# pumpController.net
KiCad netlist of a schematic drawn in Altium Designer
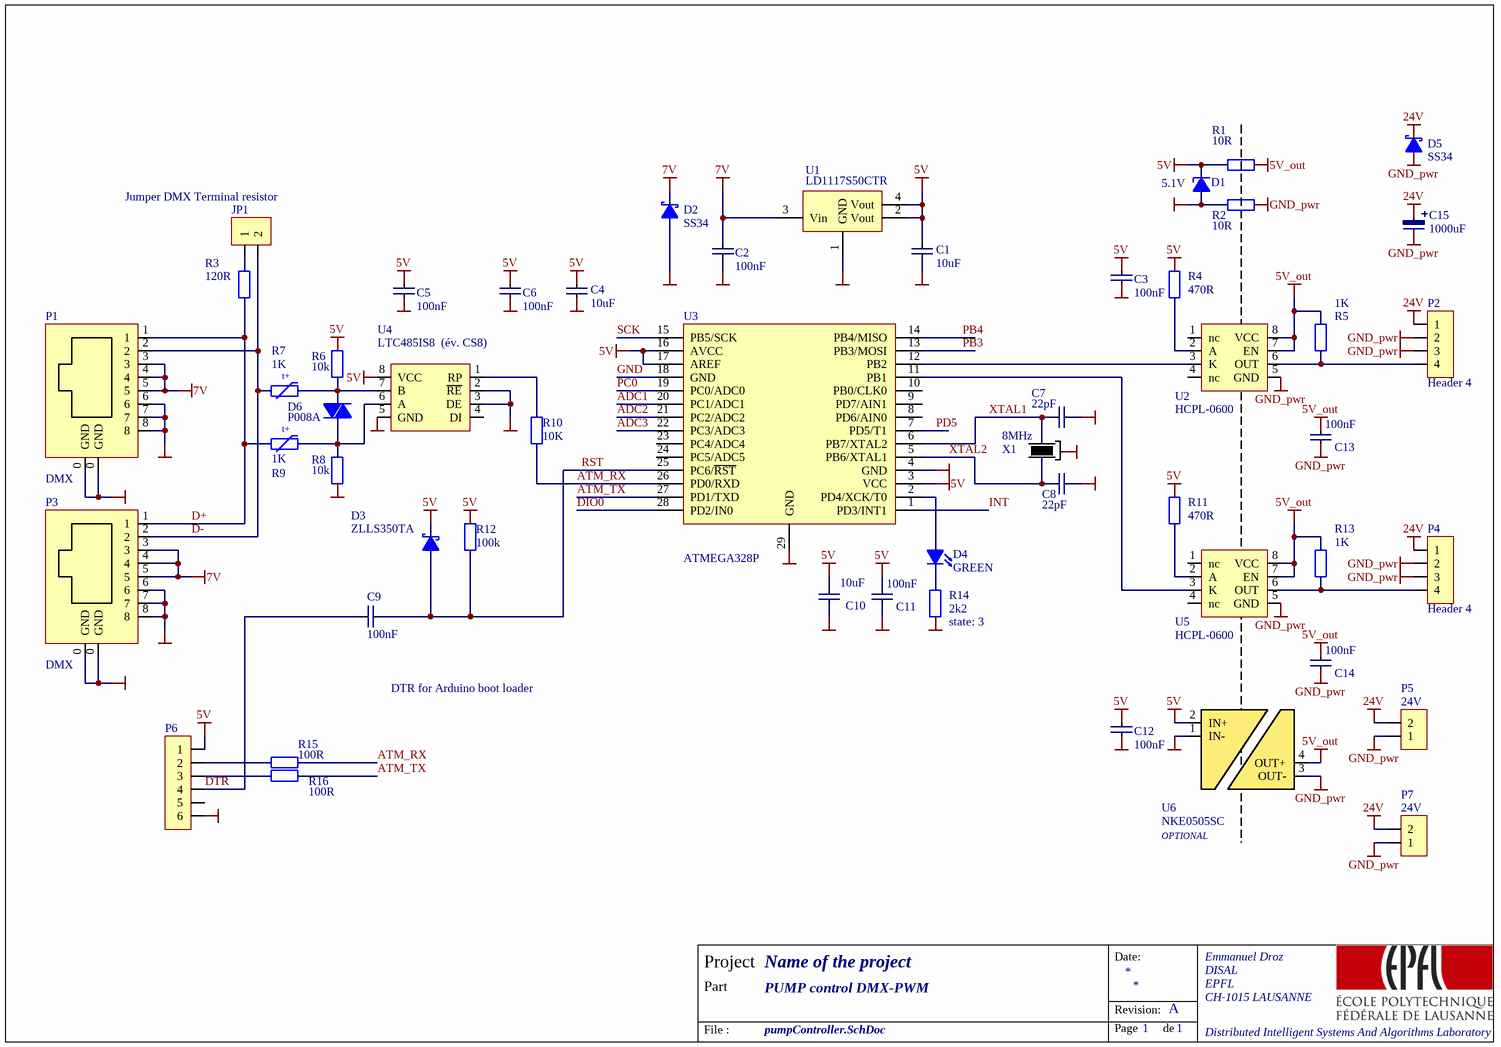
[diagram p0: pumpController.SchDoc]

(export (version "E")
  (design (tool "Eeschema 10.0.6"))
  (components
    (comp (ref "C1")
      (value "10uF")
      (footprint "SwissArmyKnife:0805")
      (description "Capacitor")
      (libsource (lib "SwissArmyKnife") (part "C"))
    )
    (comp (ref "C2")
      (value "100nF")
      (footprint "SwissArmyKnife:0603")
      (description "Capacitor")
      (libsource (lib "SwissArmyKnife") (part "C"))
    )
    (comp (ref "C3")
      (value "100nF")
      (footprint "SwissArmyKnife:0603")
      (description "Capacitor")
      (libsource (lib "SwissArmyKnife") (part "C"))
    )
    (comp (ref "C4")
      (value "10uF")
      (footprint "SwissArmyKnife:0805")
      (description "Capacitor")
      (libsource (lib "SwissArmyKnife") (part "C"))
    )
    (comp (ref "C5")
      (value "100nF")
      (footprint "SwissArmyKnife:0603")
      (description "Capacitor")
      (libsource (lib "SwissArmyKnife") (part "C"))
    )
    (comp (ref "C6")
      (value "100nF")
      (footprint "SwissArmyKnife:0603")
      (description "Capacitor")
      (libsource (lib "SwissArmyKnife") (part "C"))
    )
    (comp (ref "C7")
      (value "22pF")
      (footprint "SwissArmyKnife:0603")
      (description "Capacitor")
      (libsource (lib "SwissArmyKnife") (part "C"))
    )
    (comp (ref "C8")
      (value "22pF")
      (footprint "SwissArmyKnife:0603")
      (description "Capacitor")
      (libsource (lib "SwissArmyKnife") (part "C"))
    )
    (comp (ref "C9")
      (value "100nF")
      (footprint "SwissArmyKnife:0603")
      (description "Capacitor")
      (libsource (lib "SwissArmyKnife") (part "C"))
    )
    (comp (ref "C10")
      (value "10uF")
      (footprint "SwissArmyKnife:0805")
      (description "Capacitor")
      (libsource (lib "SwissArmyKnife") (part "C"))
    )
    (comp (ref "C11")
      (value "100nF")
      (footprint "SwissArmyKnife:0603")
      (description "Capacitor")
      (libsource (lib "SwissArmyKnife") (part "C"))
    )
    (comp (ref "C12")
      (value "100nF")
      (footprint "SwissArmyKnife:0603")
      (description "Capacitor")
      (libsource (lib "SwissArmyKnife") (part "C"))
    )
    (comp (ref "C13")
      (value "100nF")
      (footprint "SwissArmyKnife:0603")
      (description "Capacitor")
      (libsource (lib "SwissArmyKnife") (part "C"))
    )
    (comp (ref "C14")
      (value "100nF")
      (footprint "SwissArmyKnife:0603")
      (description "Capacitor")
      (libsource (lib "SwissArmyKnife") (part "C"))
    )
    (comp (ref "C15")
      (value "1000uF")
      (footprint "CapaRadialD12.5H20F5")
      (description "Capacitor")
      (libsource (lib "SwissArmyKnife") (part "Cp"))
    )
    (comp (ref "D1")
      (value "5.1V")
      (footprint "MELF")
      (description "Diode")
      (fields (field (name "Comment") "not mounted"))
      (libsource (lib "electroz") (part "D_Zener"))
    )
    (comp (ref "D2")
      (value "SS34")
      (footprint "swissarmyknife:MELF")
      (description "Schottky Diode 1A 0.5V 20V")
      (fields (field (name "NAME") "SS34"))
      (libsource (lib "disaldb") (part "D_schottky"))
    )
    (comp (ref "D3")
      (value "ZLLS350TA")
      (footprint "0603pol")
      (description "Shottky diode")
      (libsource (lib "SwissArmyKnife") (part "D_schottky"))
    )
    (comp (ref "D4")
      (value "GREEN")
      (footprint "SwissArmyKnife:0805pol")
      (description "LED green")
      (libsource (lib "SwissArmyKnife") (part "LED"))
    )
    (comp (ref "D5")
      (value "SS34")
      (footprint "swissarmyknife:MELF")
      (description "Schottky Diode 1A 0.5V 20V")
      (fields (field (name "NAME") "SS34"))
      (libsource (lib "disaldb") (part "D_schottky"))
    )
    (comp (ref "D6")
      (value "P008A")
      (footprint "DO-214")
      (description "Diac")
      (libsource (lib "SwissArmyKnife") (part "D_Diac"))
    )
    (comp (ref "JP1")
      (value "Jumper DMX Terminal resistor")
      (footprint "electroz:Jumper")
      (description "Header, 4-Pin, Dual row")
      (libsource (lib "electroz") (part "Header 2"))
    )
    (comp (ref "P1")
      (value "DMX")
      (footprint "SwissArmyKnife:RJ45__socket_right")
      (libsource (lib "SwissArmyKnife") (part "RJ45"))
    )
    (comp (ref "P2")
      (value "Header 4")
      (footprint "electroz:PHO_3.81_180_4x")
      (description "Header, 4-Pin, single row")
      (fields (field (name "PUBLISHER") "Altium Limited"))
      (libsource (lib "electroz") (part "Header 4"))
    )
    (comp (ref "P3")
      (value "DMX")
      (footprint "SwissArmyKnife:RJ45__socket_right")
      (libsource (lib "SwissArmyKnife") (part "RJ45"))
    )
    (comp (ref "P4")
      (value "Header 4")
      (footprint "electroz:PHO_3.81_180_4x")
      (description "Header, 4-Pin, single row")
      (fields (field (name "PUBLISHER") "Altium Limited"))
      (libsource (lib "electroz") (part "Header 4"))
    )
    (comp (ref "P5")
      (value "24V")
      (footprint "electroz:ALIME 5_08 180")
      (description "Header, 4-Pin, Dual row")
      (fields (field (name "PUBLISHER") "Altium Limited"))
      (libsource (lib "electroz") (part "Header 2"))
    )
    (comp (ref "P6")
      (value "Header 6")
      (footprint "Header6_1.25_micro_JST_Axial")
      (description "Header,6-Pin")
      (fields (field (name "PUBLISHER") "Altium Limited"))
      (libsource (lib "SwissArmyKnife") (part "Header 6"))
    )
    (comp (ref "P7")
      (value "24V")
      (footprint "electroz:ALIME 5_08 180")
      (description "Header, 4-Pin, Dual row")
      (fields (field (name "PUBLISHER") "Altium Limited"))
      (libsource (lib "electroz") (part "Header 2"))
    )
    (comp (ref "R1")
      (value "10R")
      (footprint "swissarmyknife:0603")
      (description "Resistor")
      (libsource (lib "") (part "R_2"))
    )
    (comp (ref "R2")
      (value "10R")
      (footprint "swissarmyknife:0603")
      (description "Resistor")
      (libsource (lib "") (part "R_2"))
    )
    (comp (ref "R3")
      (value "120R")
      (footprint "swissarmyknife:1206")
      (description "Resistor")
      (libsource (lib "") (part "R_1"))
    )
    (comp (ref "R4")
      (value "470R")
      (footprint "swissarmyknife:0603")
      (description "Resistor")
      (libsource (lib "") (part "R_1"))
    )
    (comp (ref "R5")
      (value "1K")
      (footprint "swissarmyknife:0603")
      (description "Resistor")
      (libsource (lib "") (part "R_1"))
    )
    (comp (ref "R6")
      (value "10k")
      (footprint "swissarmyknife:0603")
      (description "Resistor")
      (libsource (lib "") (part "R_1"))
    )
    (comp (ref "R7")
      (value "1K")
      (footprint "swissarmyknife:MZ6")
      (description "Resistor PTC")
      (libsource (lib "SwissArmyKnife") (part "R_ptc"))
    )
    (comp (ref "R8")
      (value "10k")
      (footprint "swissarmyknife:0603")
      (description "Resistor")
      (libsource (lib "") (part "R_1"))
    )
    (comp (ref "R9")
      (value "1K")
      (footprint "swissarmyknife:MZ6")
      (description "Resistor PTC")
      (libsource (lib "SwissArmyKnife") (part "R_ptc"))
    )
    (comp (ref "R10")
      (value "10K")
      (footprint "swissarmyknife:0603")
      (description "Resistor")
      (libsource (lib "") (part "R_1"))
    )
    (comp (ref "R11")
      (value "470R")
      (footprint "swissarmyknife:0603")
      (description "Resistor")
      (libsource (lib "") (part "R_1"))
    )
    (comp (ref "R12")
      (value "100k")
      (footprint "swissarmyknife:0603")
      (description "Resistor")
      (libsource (lib "") (part "R_2"))
    )
    (comp (ref "R13")
      (value "1K")
      (footprint "swissarmyknife:0603")
      (description "Resistor")
      (libsource (lib "") (part "R_1"))
    )
    (comp (ref "R14")
      (value "2k2")
      (footprint "swissarmyknife:0603")
      (description "Resistor")
      (fields (field (name "STATE") "3"))
      (libsource (lib "") (part "R_1"))
    )
    (comp (ref "R15")
      (value "100R")
      (footprint "swissarmyknife:0603")
      (description "Resistor")
      (libsource (lib "SwissArmyKnife") (part "R"))
    )
    (comp (ref "R16")
      (value "100R")
      (footprint "swissarmyknife:0603")
      (description "Resistor")
      (libsource (lib "SwissArmyKnife") (part "R"))
    )
    (comp (ref "U1")
      (value "LD1117S50CTR")
      (footprint "SOT-223")
      (description "Linear regulator")
      (fields (field (name "NAME") "LD1117S50CTR"))
      (libsource (lib "SwissArmyKnife") (part "STAB_x17"))
    )
    (comp (ref "U2")
      (value "HCPL-0600")
      (footprint "electroz:so-8")
      (description "Logical optocoupler single SO8")
      (libsource (lib "electroz") (part "HCPL-0600"))
    )
    (comp (ref "U3")
      (value "ATMEGA328P")
      (footprint "ATM328P_MMH")
      (libsource (lib "LoRa_I2C_Lib") (part "ATM328P"))
    )
    (comp (ref "U4")
      (value "LTC485IS8  (év. CS8)")
      (footprint "SwissArmyKnife:so-8")
      (libsource (lib "electroz") (part "LTC485CS8"))
    )
    (comp (ref "U5")
      (value "HCPL-0600")
      (footprint "electroz:so-8")
      (description "Logical optocoupler single SO8")
      (libsource (lib "electroz") (part "HCPL-0600"))
    )
    (comp (ref "U6")
      (value "NKE0505SC")
      (footprint "SIL4")
      (description "Isolated power supply")
      (libsource (lib "electroz") (part "DCDCisolated"))
    )
    (comp (ref "X1") (value "8MHz") (footprint "osc") (libsource (lib "SwissArmyKnife") (part "Quartz")))
  )
  (nets
    (net (code "1") (name "/ADC1") (class "Default")
      (node (ref "U3") (pin "20") (pinfunction "PC1/ADC1_20") (pintype "passive"))
    )
    (net (code "2") (name "/ADC2") (class "Default")
      (node (ref "U3") (pin "21") (pinfunction "PC2/ADC2_21") (pintype "passive"))
    )
    (net (code "3") (name "/ADC3") (class "Default")
      (node (ref "U3") (pin "22") (pinfunction "PC3/ADC3_22") (pintype "passive"))
    )
    (net (code "4") (name "/ATM_RX") (class "Default")
      (node (ref "R10") (pin "2") (pinfunction "2_2") (pintype "passive"))
      (node (ref "R15") (pin "2") (pinfunction "2_2") (pintype "passive"))
      (node (ref "U3") (pin "26") (pinfunction "PD0/RXD_26") (pintype "passive"))
    )
    (net (code "5") (name "/ATM_TX") (class "Default")
      (node (ref "R16") (pin "2") (pinfunction "2_2") (pintype "passive"))
      (node (ref "U3") (pin "27") (pinfunction "PD1/TXD_27") (pintype "passive"))
    )
    (net (code "6") (name "/D+") (class "Default")
      (node (ref "P1") (pin "1") (pinfunction "1_1") (pintype "passive"))
      (node (ref "P3") (pin "1") (pinfunction "1_1") (pintype "passive"))
      (node (ref "R3") (pin "2") (pinfunction "2_2") (pintype "passive"))
      (node (ref "R9") (pin "1") (pinfunction "1_1") (pintype "passive"))
    )
    (net (code "7") (name "/D-") (class "Default")
      (node (ref "JP1") (pin "2") (pinfunction "2_2") (pintype "passive"))
      (node (ref "P1") (pin "2") (pinfunction "2_2") (pintype "passive"))
      (node (ref "P3") (pin "2") (pinfunction "2_2") (pintype "passive"))
      (node (ref "R7") (pin "1") (pinfunction "1_1") (pintype "passive"))
    )
    (net (code "8") (name "/DIO0") (class "Default")
      (node (ref "U3") (pin "28") (pinfunction "PD2/IN0_28") (pintype "passive"))
    )
    (net (code "9") (name "/DTR") (class "Default")
      (node (ref "C9") (pin "2") (pinfunction "2_2") (pintype "passive"))
      (node (ref "P6") (pin "4") (pinfunction "4_4") (pintype "passive"))
    )
    (net (code "10") (name "/INT") (class "Default")
      (node (ref "U3") (pin "1") (pinfunction "PD3/INT1_1") (pintype "passive"))
    )
    (net (code "11") (name "/PB3") (class "Default")
      (node (ref "U3") (pin "13") (pinfunction "PB3/MOSI_13") (pintype "passive"))
    )
    (net (code "12") (name "/PB4") (class "Default")
      (node (ref "U3") (pin "14") (pinfunction "PB4/MISO_14") (pintype "passive"))
    )
    (net (code "13") (name "/PC0") (class "Default")
      (node (ref "U3") (pin "19") (pinfunction "PC0/ADC0_19") (pintype "passive"))
    )
    (net (code "14") (name "/PD5") (class "Default")
      (node (ref "U3") (pin "7") (pinfunction "PD5/T1_7") (pintype "passive"))
    )
    (net (code "15") (name "/RST") (class "Default")
      (node (ref "C9") (pin "1") (pinfunction "1_1") (pintype "passive"))
      (node (ref "D3") (pin "1") (pinfunction "A_1") (pintype "passive"))
      (node (ref "R12") (pin "1") (pinfunction "1_1") (pintype "passive"))
      (node (ref "U3") (pin "25") (pinfunction "PC6/~{RST}_25") (pintype "passive"))
    )
    (net (code "16") (name "/SCK") (class "Default")
      (node (ref "U3") (pin "15") (pinfunction "PB5/SCK_15") (pintype "passive"))
    )
    (net (code "17") (name "/XTAL1") (class "Default")
      (node (ref "C7") (pin "1") (pinfunction "1_1") (pintype "passive"))
      (node (ref "U3") (pin "6") (pinfunction "PB7/XTAL2_6") (pintype "passive"))
      (node (ref "X1") (pin "1") (pinfunction "1_1") (pintype "passive"))
    )
    (net (code "18") (name "/XTAL2") (class "Default")
      (node (ref "C8") (pin "1") (pinfunction "1_1") (pintype "passive"))
      (node (ref "U3") (pin "5") (pinfunction "PB6/XTAL1_5") (pintype "passive"))
      (node (ref "X1") (pin "2") (pinfunction "2_2") (pintype "passive"))
    )
    (net (code "19") (name "5V") (class "Default")
      (node (ref "C1") (pin "1") (pinfunction "1_1") (pintype "passive"))
      (node (ref "C10") (pin "1") (pinfunction "1_1") (pintype "passive"))
      (node (ref "C11") (pin "1") (pinfunction "1_1") (pintype "passive"))
      (node (ref "C12") (pin "2") (pinfunction "2_2") (pintype "passive"))
      (node (ref "C3") (pin "2") (pinfunction "2_2") (pintype "passive"))
      (node (ref "C4") (pin "1") (pinfunction "1_1") (pintype "passive"))
      (node (ref "C5") (pin "2") (pinfunction "2_2") (pintype "passive"))
      (node (ref "C6") (pin "2") (pinfunction "2_2") (pintype "passive"))
      (node (ref "D1") (pin "2") (pinfunction "K_2") (pintype "passive"))
      (node (ref "D3") (pin "2") (pinfunction "K_2") (pintype "passive"))
      (node (ref "P6") (pin "1") (pinfunction "1_1") (pintype "passive"))
      (node (ref "R1") (pin "1") (pinfunction "1_1") (pintype "passive"))
      (node (ref "R11") (pin "1") (pinfunction "1_1") (pintype "passive"))
      (node (ref "R12") (pin "2") (pinfunction "2_2") (pintype "passive"))
      (node (ref "R4") (pin "1") (pinfunction "1_1") (pintype "passive"))
      (node (ref "R6") (pin "1") (pinfunction "1_1") (pintype "passive"))
      (node (ref "U1") (pin "2") (pinfunction "Vout_2") (pintype "power_in"))
      (node (ref "U1") (pin "4") (pinfunction "Vout_4") (pintype "passive"))
      (node (ref "U3") (pin "16") (pinfunction "AVCC_16") (pintype "passive"))
      (node (ref "U3") (pin "17") (pinfunction "AREF_17") (pintype "passive"))
      (node (ref "U3") (pin "3") (pinfunction "VCC_3") (pintype "passive"))
      (node (ref "U4") (pin "8") (pinfunction "VCC_8") (pintype "passive"))
      (node (ref "U6") (pin "2") (pinfunction "IN+_2") (pintype "passive"))
    )
    (net (code "20") (name "5V_out") (class "Default")
      (node (ref "C13") (pin "1") (pinfunction "1_1") (pintype "passive"))
      (node (ref "C14") (pin "1") (pinfunction "1_1") (pintype "passive"))
      (node (ref "R1") (pin "2") (pinfunction "2_2") (pintype "passive"))
      (node (ref "R13") (pin "1") (pinfunction "1_1") (pintype "passive"))
      (node (ref "R5") (pin "1") (pinfunction "1_1") (pintype "passive"))
      (node (ref "U2") (pin "7") (pinfunction "EN_7") (pintype "passive"))
      (node (ref "U2") (pin "8") (pinfunction "VCC_8") (pintype "passive"))
      (node (ref "U5") (pin "7") (pinfunction "EN_7") (pintype "passive"))
      (node (ref "U5") (pin "8") (pinfunction "VCC_8") (pintype "passive"))
      (node (ref "U6") (pin "4") (pinfunction "OUT+_4") (pintype "passive"))
    )
    (net (code "21") (name "7V") (class "Default")
      (node (ref "C2") (pin "2") (pinfunction "2_2") (pintype "passive"))
      (node (ref "D2") (pin "2") (pinfunction "K_2") (pintype "passive"))
      (node (ref "P1") (pin "3") (pinfunction "3_3") (pintype "passive"))
      (node (ref "P1") (pin "4") (pinfunction "4_4") (pintype "passive"))
      (node (ref "P1") (pin "5") (pinfunction "5_5") (pintype "passive"))
      (node (ref "P3") (pin "3") (pinfunction "3_3") (pintype "passive"))
      (node (ref "P3") (pin "4") (pinfunction "4_4") (pintype "passive"))
      (node (ref "P3") (pin "5") (pinfunction "5_5") (pintype "passive"))
      (node (ref "U1") (pin "3") (pinfunction "Vin_3") (pintype "power_in"))
    )
    (net (code "22") (name "24V") (class "Default")
      (node (ref "C15") (pin "2") (pinfunction "2_2") (pintype "passive"))
      (node (ref "D5") (pin "2") (pinfunction "K_2") (pintype "passive"))
      (node (ref "P2") (pin "1") (pinfunction "1_1") (pintype "passive"))
      (node (ref "P4") (pin "1") (pinfunction "1_1") (pintype "passive"))
      (node (ref "P5") (pin "2") (pinfunction "2_2") (pintype "passive"))
      (node (ref "P7") (pin "2") (pinfunction "2_2") (pintype "passive"))
    )
    (net (code "23") (name "GND") (class "Default")
      (node (ref "C1") (pin "2") (pinfunction "2_2") (pintype "passive"))
      (node (ref "C10") (pin "2") (pinfunction "2_2") (pintype "passive"))
      (node (ref "C11") (pin "2") (pinfunction "2_2") (pintype "passive"))
      (node (ref "C12") (pin "1") (pinfunction "1_1") (pintype "passive"))
      (node (ref "C2") (pin "1") (pinfunction "1_1") (pintype "passive"))
      (node (ref "C3") (pin "1") (pinfunction "1_1") (pintype "passive"))
      (node (ref "C4") (pin "2") (pinfunction "2_2") (pintype "passive"))
      (node (ref "C5") (pin "1") (pinfunction "1_1") (pintype "passive"))
      (node (ref "C6") (pin "1") (pinfunction "1_1") (pintype "passive"))
      (node (ref "C7") (pin "2") (pinfunction "2_2") (pintype "passive"))
      (node (ref "C8") (pin "2") (pinfunction "2_2") (pintype "passive"))
      (node (ref "D1") (pin "1") (pinfunction "A_1") (pintype "passive"))
      (node (ref "D2") (pin "1") (pinfunction "A_1") (pintype "passive"))
      (node (ref "P1") (pin "0") (pinfunction "GND_0") (pintype "passive"))
      (node (ref "P1") (pin "6") (pinfunction "6_6") (pintype "passive"))
      (node (ref "P1") (pin "7") (pinfunction "7_7") (pintype "passive"))
      (node (ref "P1") (pin "8") (pinfunction "8_8") (pintype "passive"))
      (node (ref "P3") (pin "0") (pinfunction "GND_0") (pintype "passive"))
      (node (ref "P3") (pin "6") (pinfunction "6_6") (pintype "passive"))
      (node (ref "P3") (pin "7") (pinfunction "7_7") (pintype "passive"))
      (node (ref "P3") (pin "8") (pinfunction "8_8") (pintype "passive"))
      (node (ref "P6") (pin "6") (pinfunction "6_6") (pintype "passive"))
      (node (ref "R14") (pin "2") (pinfunction "2_2") (pintype "passive"))
      (node (ref "R2") (pin "1") (pinfunction "1_1") (pintype "passive"))
      (node (ref "R8") (pin "2") (pinfunction "2_2") (pintype "passive"))
      (node (ref "U1") (pin "1") (pinfunction "GND_1") (pintype "passive"))
      (node (ref "U3") (pin "18") (pinfunction "GND_18") (pintype "passive"))
      (node (ref "U3") (pin "29") (pinfunction "GND_29") (pintype "passive"))
      (node (ref "U3") (pin "4") (pinfunction "GND_4") (pintype "passive"))
      (node (ref "U4") (pin "2") (pinfunction "~{RE}_2") (pintype "passive"))
      (node (ref "U4") (pin "3") (pinfunction "DE_3") (pintype "passive"))
      (node (ref "U4") (pin "5") (pinfunction "GND_5") (pintype "passive"))
      (node (ref "U6") (pin "1") (pinfunction "IN-_1") (pintype "passive"))
      (node (ref "X1") (pin "3") (pinfunction "3_3") (pintype "passive"))
    )
    (net (code "24") (name "GND_pwr") (class "Default")
      (node (ref "C13") (pin "2") (pinfunction "2_2") (pintype "passive"))
      (node (ref "C14") (pin "2") (pinfunction "2_2") (pintype "passive"))
      (node (ref "C15") (pin "1") (pinfunction "1_1") (pintype "passive"))
      (node (ref "D5") (pin "1") (pinfunction "A_1") (pintype "passive"))
      (node (ref "P2") (pin "2") (pinfunction "2_2") (pintype "passive"))
      (node (ref "P2") (pin "3") (pinfunction "3_3") (pintype "passive"))
      (node (ref "P4") (pin "2") (pinfunction "2_2") (pintype "passive"))
      (node (ref "P4") (pin "3") (pinfunction "3_3") (pintype "passive"))
      (node (ref "P5") (pin "1") (pinfunction "1_1") (pintype "passive"))
      (node (ref "P7") (pin "1") (pinfunction "1_1") (pintype "passive"))
      (node (ref "R2") (pin "2") (pinfunction "2_2") (pintype "passive"))
      (node (ref "U2") (pin "5") (pinfunction "GND_5") (pintype "passive"))
      (node (ref "U5") (pin "5") (pinfunction "GND_5") (pintype "passive"))
      (node (ref "U6") (pin "3") (pinfunction "OUT-_3") (pintype "passive"))
    )
    (net (code "25") (name "Net-(D4-A)") (class "Default")
      (node (ref "D4") (pin "1") (pinfunction "A_1") (pintype "passive"))
      (node (ref "U3") (pin "2") (pinfunction "PD4/XCK/T0_2") (pintype "passive"))
    )
    (net (code "26") (name "Net-(D4-K)") (class "Default")
      (node (ref "D4") (pin "2") (pinfunction "K_2") (pintype "passive"))
      (node (ref "R14") (pin "1") (pinfunction "1_1") (pintype "passive"))
    )
    (net (code "27") (name "Net-(D6-A)") (class "Default")
      (node (ref "D6") (pin "1") (pinfunction "A_1") (pintype "passive"))
      (node (ref "R6") (pin "2") (pinfunction "2_2") (pintype "passive"))
      (node (ref "R7") (pin "2") (pinfunction "2_2") (pintype "passive"))
      (node (ref "U4") (pin "7") (pinfunction "B_7") (pintype "passive"))
    )
    (net (code "28") (name "Net-(D6-K)") (class "Default")
      (node (ref "D6") (pin "2") (pinfunction "K_2") (pintype "passive"))
      (node (ref "R8") (pin "1") (pinfunction "1_1") (pintype "passive"))
      (node (ref "R9") (pin "2") (pinfunction "2_2") (pintype "passive"))
      (node (ref "U4") (pin "6") (pinfunction "A_6") (pintype "passive"))
    )
    (net (code "29") (name "Net-(JP1-Pad1)") (class "Default")
      (node (ref "JP1") (pin "1") (pinfunction "1_1") (pintype "passive"))
      (node (ref "R3") (pin "1") (pinfunction "1_1") (pintype "passive"))
    )
    (net (code "30") (name "Net-(P6-Pad2)") (class "Default")
      (node (ref "P6") (pin "2") (pinfunction "2_2") (pintype "passive"))
      (node (ref "R15") (pin "1") (pinfunction "1_1") (pintype "passive"))
    )
    (net (code "31") (name "Net-(P6-Pad3)") (class "Default")
      (node (ref "P6") (pin "3") (pinfunction "3_3") (pintype "passive"))
      (node (ref "R16") (pin "1") (pinfunction "1_1") (pintype "passive"))
    )
    (net (code "32") (name "Net-(U2-A)") (class "Default")
      (node (ref "R4") (pin "2") (pinfunction "2_2") (pintype "passive"))
      (node (ref "U2") (pin "2") (pinfunction "A_2") (pintype "passive"))
    )
    (net (code "33") (name "Net-(U2-K)") (class "Default")
      (node (ref "U2") (pin "3") (pinfunction "K_3") (pintype "passive"))
      (node (ref "U3") (pin "12") (pinfunction "PB2_12") (pintype "passive"))
    )
    (net (code "34") (name "Net-(U2-OUT)") (class "Default")
      (node (ref "P2") (pin "4") (pinfunction "4_4") (pintype "passive"))
      (node (ref "R5") (pin "2") (pinfunction "2_2") (pintype "passive"))
      (node (ref "U2") (pin "6") (pinfunction "OUT_6") (pintype "passive"))
    )
    (net (code "35") (name "Net-(U3-PB1)") (class "Default")
      (node (ref "U3") (pin "11") (pinfunction "PB1_11") (pintype "passive"))
      (node (ref "U5") (pin "3") (pinfunction "K_3") (pintype "passive"))
    )
    (net (code "36") (name "Net-(U4-RP)") (class "Default")
      (node (ref "R10") (pin "1") (pinfunction "1_1") (pintype "passive"))
      (node (ref "U4") (pin "1") (pinfunction "RP_1") (pintype "passive"))
    )
    (net (code "37") (name "Net-(U5-A)") (class "Default")
      (node (ref "R11") (pin "2") (pinfunction "2_2") (pintype "passive"))
      (node (ref "U5") (pin "2") (pinfunction "A_2") (pintype "passive"))
    )
    (net (code "38") (name "Net-(U5-OUT)") (class "Default")
      (node (ref "P4") (pin "4") (pinfunction "4_4") (pintype "passive"))
      (node (ref "R13") (pin "2") (pinfunction "2_2") (pintype "passive"))
      (node (ref "U5") (pin "6") (pinfunction "OUT_6") (pintype "passive"))
    )
    (net (code "39") (name "unconnected-(P6-Pad5)") (class "Default")
      (node (ref "P6") (pin "5") (pinfunction "5_5") (pintype "passive"))
    )
    (net (code "40") (name "unconnected-(U1-N{slash}C-Pad4)") (class "Default")
      (node (ref "U1") (pin "4") (pinfunction "N/C_4") (pintype "passive"))
    )
    (net (code "41") (name "unconnected-(U2-nc-Pad1)") (class "Default")
      (node (ref "U2") (pin "1") (pinfunction "nc_1") (pintype "passive"))
    )
    (net (code "42") (name "unconnected-(U2-nc-Pad4)") (class "Default")
      (node (ref "U2") (pin "4") (pinfunction "nc_4") (pintype "passive"))
    )
    (net (code "43") (name "unconnected-(U3-PB0{slash}CLK0-Pad10)") (class "Default")
      (node (ref "U3") (pin "10") (pinfunction "PB0/CLK0_10") (pintype "passive"))
    )
    (net (code "44") (name "unconnected-(U3-PC4{slash}ADC4-Pad23)") (class "Default")
      (node (ref "U3") (pin "23") (pinfunction "PC4/ADC4_23") (pintype "passive"))
    )
    (net (code "45") (name "unconnected-(U3-PC5{slash}ADC5-Pad24)") (class "Default")
      (node (ref "U3") (pin "24") (pinfunction "PC5/ADC5_24") (pintype "passive"))
    )
    (net (code "46") (name "unconnected-(U3-PD6{slash}AIN0-Pad8)") (class "Default")
      (node (ref "U3") (pin "8") (pinfunction "PD6/AIN0_8") (pintype "passive"))
    )
    (net (code "47") (name "unconnected-(U3-PD7{slash}AIN1-Pad9)") (class "Default")
      (node (ref "U3") (pin "9") (pinfunction "PD7/AIN1_9") (pintype "passive"))
    )
    (net (code "48") (name "unconnected-(U4-DI-Pad4)") (class "Default")
      (node (ref "U4") (pin "4") (pinfunction "DI_4") (pintype "passive"))
    )
    (net (code "49") (name "unconnected-(U5-nc-Pad1)") (class "Default")
      (node (ref "U5") (pin "1") (pinfunction "nc_1") (pintype "passive"))
    )
    (net (code "50") (name "unconnected-(U5-nc-Pad4)") (class "Default")
      (node (ref "U5") (pin "4") (pinfunction "nc_4") (pintype "passive"))
    )
  )
)
